# adjustable_biasing_pots.net
KiCad netlist of a schematic drawn in Altium Designer
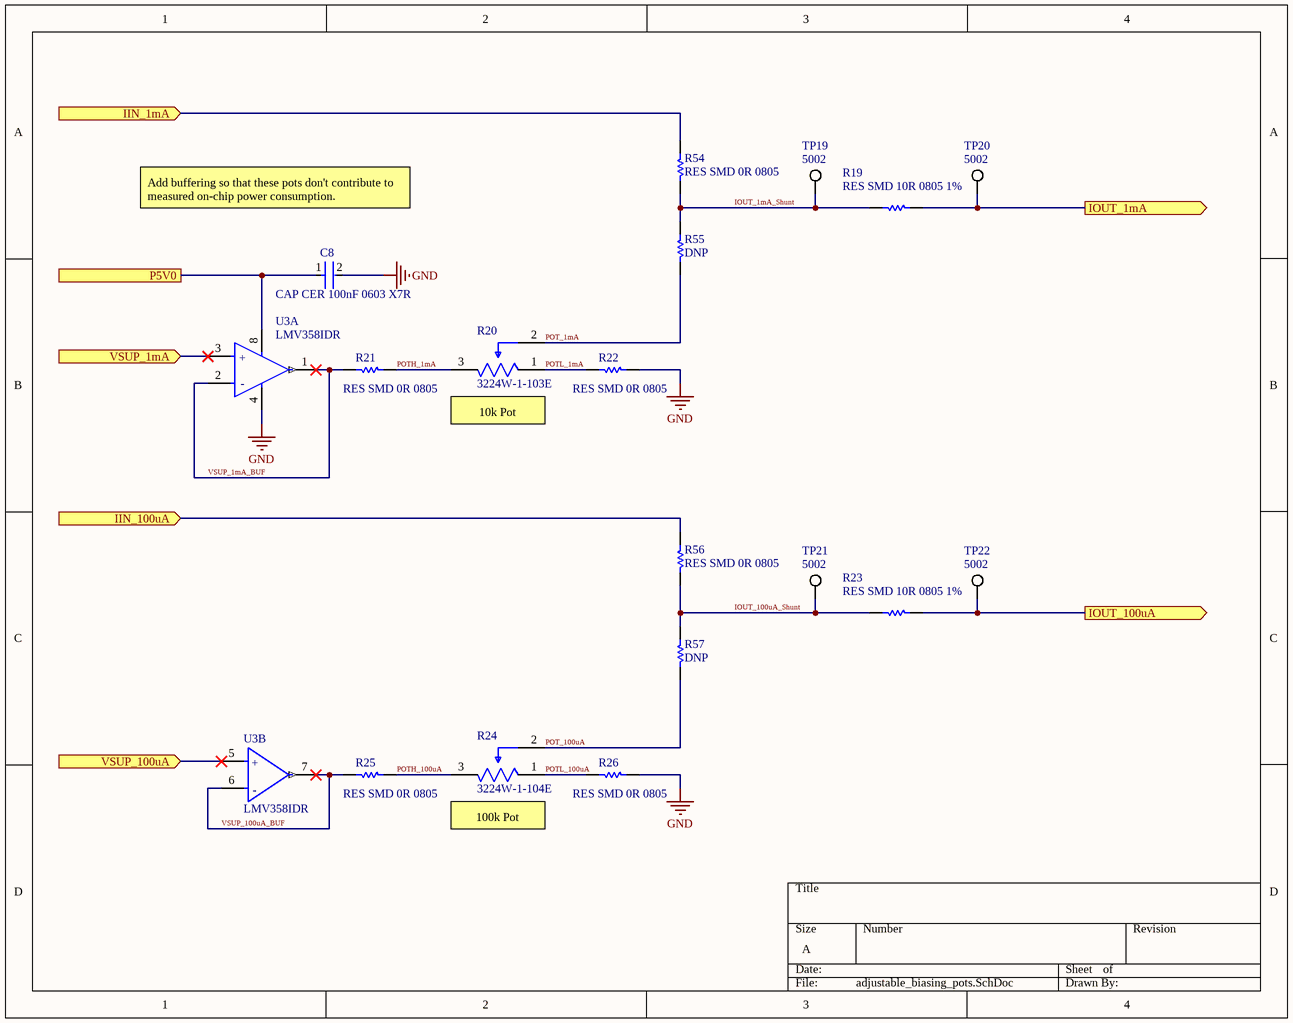
[diagram p0: adjustable_biasing_pots.SchDoc]

(export (version "E")
  (design (tool "Eeschema 10.0.6"))
  (components
    (comp (ref "C8")
      (value "CAP CER 100nF 0603 X7R")
      (footprint "FP-CC0603-DA-MFG")
      (description "CAP CER 0.1UF 16V X7R 0603")
      (fields
        (field (name "OCTOPART") "https://octopart.com/cc0603krx7r7bb104-yageo-192941")
        (field (name "TOLERANCE") "0.1")
      )
      (libsource (lib "Altium Content Vault") (part "11868f565c42a9108669ba33697ecf6"))
    )
    (comp (ref "R19")
      (value "RES SMD 10R 0805 1%")
      (footprint "RESC2013X55X40NL15T20")
      (fields (field (name "MANUFACTURER") "Vishay Dale") (field (name "PART NUMBER") "TNPW0805100RBEEA"))
      (libsource (lib "Altium Content Vault") (part "RES"))
    )
    (comp (ref "R20")
      (value "3224W-1-103E")
      (footprint "FP-3224W-MFG")
      (description "TRIMMER 10K OHM 0.25W J LEAD TOP")
      (fields (field (name "TOLERANCE") "10%") (field (name "MANUFACTURER") "Bourns"))
      (libsource (lib "Altium Content Vault") (part "83d3d349ed884d1db45cec512f27eb6"))
    )
    (comp (ref "R21")
      (value "RES SMD 0R 0805")
      (footprint "RESC2013X55X40NL15T20")
      (fields (field (name "MANUFACTURER") "Vishay Dale") (field (name "PART NUMBER") "TNPW0805100RBEEA"))
      (libsource (lib "Altium Content Vault") (part "RES"))
    )
    (comp (ref "R22")
      (value "RES SMD 0R 0805")
      (footprint "RESC2013X55X40NL15T20")
      (fields (field (name "MANUFACTURER") "Vishay Dale") (field (name "PART NUMBER") "TNPW0805100RBEEA"))
      (libsource (lib "Altium Content Vault") (part "RES"))
    )
    (comp (ref "R23")
      (value "RES SMD 10R 0805 1%")
      (footprint "RESC2013X55X40NL15T20")
      (fields (field (name "MANUFACTURER") "Vishay Dale") (field (name "PART NUMBER") "TNPW0805100RBEEA"))
      (libsource (lib "Altium Content Vault") (part "RES"))
    )
    (comp (ref "R24")
      (value "3224W-1-104E")
      (footprint "FP-3224W-MFG")
      (description "TRIMMER 10K OHM 0.25W J LEAD TOP")
      (fields (field (name "TOLERANCE") "10%") (field (name "MANUFACTURER") "Bourns"))
      (libsource (lib "Altium Content Vault") (part "83d3d349ed884d1db45cec512f27eb6"))
    )
    (comp (ref "R25")
      (value "RES SMD 0R 0805")
      (footprint "RESC2013X55X40NL15T20")
      (fields (field (name "MANUFACTURER") "Vishay Dale") (field (name "PART NUMBER") "TNPW0805100RBEEA"))
      (libsource (lib "Altium Content Vault") (part "RES"))
    )
    (comp (ref "R26")
      (value "RES SMD 0R 0805")
      (footprint "RESC2013X55X40NL15T20")
      (fields (field (name "MANUFACTURER") "Vishay Dale") (field (name "PART NUMBER") "TNPW0805100RBEEA"))
      (libsource (lib "Altium Content Vault") (part "RES"))
    )
    (comp (ref "R54")
      (value "RES SMD 0R 0805")
      (footprint "RESC2013X55X40NL15T20")
      (fields (field (name "MANUFACTURER") "Vishay Dale") (field (name "PART NUMBER") "TNPW0805100RBEEA"))
      (libsource (lib "Altium Content Vault") (part "RES"))
    )
    (comp (ref "R55")
      (value "DNP")
      (footprint "RESC2013X55X40NL15T20")
      (fields (field (name "MANUFACTURER") "Vishay Dale") (field (name "PART NUMBER") "TNPW0805100RBEEA"))
      (libsource (lib "Altium Content Vault") (part "RES"))
    )
    (comp (ref "R56")
      (value "RES SMD 0R 0805")
      (footprint "RESC2013X55X40NL15T20")
      (fields (field (name "MANUFACTURER") "Vishay Dale") (field (name "PART NUMBER") "TNPW0805100RBEEA"))
      (libsource (lib "Altium Content Vault") (part "RES"))
    )
    (comp (ref "R57")
      (value "DNP")
      (footprint "RESC2013X55X40NL15T20")
      (fields (field (name "MANUFACTURER") "Vishay Dale") (field (name "PART NUMBER") "TNPW0805100RBEEA"))
      (libsource (lib "Altium Content Vault") (part "RES"))
    )
    (comp (ref "TP19")
      (value "5002")
      (footprint "KSTN-5002")
      (description "Test Point, White, 1-Pin THD, RoHS, Bulk")
      (fields (field (name "MANUFACTURER") "KeystoneElectronics"))
      (libsource (lib "Altium Content Vault") (part "KSTN-TP-5002"))
    )
    (comp (ref "TP20")
      (value "5002")
      (footprint "KSTN-5002")
      (description "Test Point, White, 1-Pin THD, RoHS, Bulk")
      (fields (field (name "MANUFACTURER") "KeystoneElectronics"))
      (libsource (lib "Altium Content Vault") (part "KSTN-TP-5002"))
    )
    (comp (ref "TP21")
      (value "5002")
      (footprint "KSTN-5002")
      (description "Test Point, White, 1-Pin THD, RoHS, Bulk")
      (fields (field (name "MANUFACTURER") "KeystoneElectronics"))
      (libsource (lib "Altium Content Vault") (part "KSTN-TP-5002"))
    )
    (comp (ref "TP22")
      (value "5002")
      (footprint "KSTN-5002")
      (description "Test Point, White, 1-Pin THD, RoHS, Bulk")
      (fields (field (name "MANUFACTURER") "KeystoneElectronics"))
      (libsource (lib "Altium Content Vault") (part "KSTN-TP-5002"))
    )
    (comp (ref "U3")
      (value "LMV358IDR")
      (footprint "FP-D0008A-MFG")
      (description "IC OPAMP GP 2 CIRCUIT 8SOIC")
      (libsource (lib "Altium Content Vault") (part "1f85fec4e6914445158f776dbf16c1d"))
    )
  )
  (nets
    (net (code "1") (name "/IIN_1mA") (class "Default")
      (node (ref "R54") (pin "2") (pinfunction "2_2") (pintype "passive"))
    )
    (net (code "2") (name "/IIN_100uA") (class "Default")
      (node (ref "R56") (pin "2") (pinfunction "2_2") (pintype "passive"))
    )
    (net (code "3") (name "/IOUT_1mA") (class "Default")
      (node (ref "R19") (pin "2") (pinfunction "2_2") (pintype "passive"))
      (node (ref "TP20") (pin "1") (pintype "passive"))
    )
    (net (code "4") (name "/IOUT_1mA_Shunt") (class "Default")
      (node (ref "R19") (pin "1") (pinfunction "1_1") (pintype "passive"))
      (node (ref "R54") (pin "1") (pinfunction "1_1") (pintype "passive"))
      (node (ref "R55") (pin "2") (pinfunction "2_2") (pintype "passive"))
      (node (ref "TP19") (pin "1") (pintype "passive"))
    )
    (net (code "5") (name "/IOUT_100uA") (class "Default")
      (node (ref "R23") (pin "2") (pinfunction "2_2") (pintype "passive"))
      (node (ref "TP22") (pin "1") (pintype "passive"))
    )
    (net (code "6") (name "/IOUT_100uA_Shunt") (class "Default")
      (node (ref "R23") (pin "1") (pinfunction "1_1") (pintype "passive"))
      (node (ref "R56") (pin "1") (pinfunction "1_1") (pintype "passive"))
      (node (ref "R57") (pin "2") (pinfunction "2_2") (pintype "passive"))
      (node (ref "TP21") (pin "1") (pintype "passive"))
    )
    (net (code "7") (name "/P5V0") (class "Default")
      (node (ref "C8") (pin "1") (pinfunction "1_1") (pintype "passive"))
      (node (ref "U3") (pin "8") (pinfunction "VCC+_8") (pintype "power_in"))
    )
    (net (code "8") (name "/POTH_1mA") (class "Default")
      (node (ref "R20") (pin "3") (pinfunction "CW_3") (pintype "passive"))
      (node (ref "R21") (pin "2") (pinfunction "2_2") (pintype "passive"))
    )
    (net (code "9") (name "/POTH_100uA") (class "Default")
      (node (ref "R24") (pin "3") (pinfunction "CW_3") (pintype "passive"))
      (node (ref "R25") (pin "2") (pinfunction "2_2") (pintype "passive"))
    )
    (net (code "10") (name "/POTL_1mA") (class "Default")
      (node (ref "R20") (pin "1") (pinfunction "CCW_1") (pintype "passive"))
      (node (ref "R22") (pin "1") (pinfunction "1_1") (pintype "passive"))
    )
    (net (code "11") (name "/POTL_100uA") (class "Default")
      (node (ref "R24") (pin "1") (pinfunction "CCW_1") (pintype "passive"))
      (node (ref "R26") (pin "1") (pinfunction "1_1") (pintype "passive"))
    )
    (net (code "12") (name "/POT_1mA") (class "Default")
      (node (ref "R20") (pin "2") (pinfunction "WIPER_2") (pintype "passive"))
      (node (ref "R55") (pin "1") (pinfunction "1_1") (pintype "passive"))
    )
    (net (code "13") (name "/POT_100uA") (class "Default")
      (node (ref "R24") (pin "2") (pinfunction "WIPER_2") (pintype "passive"))
      (node (ref "R57") (pin "1") (pinfunction "1_1") (pintype "passive"))
    )
    (net (code "14") (name "/VSUP_1mA") (class "Default")
      (node (ref "U3") (pin "3") (pinfunction "1IN+_3") (pintype "tri_state+no_connect"))
    )
    (net (code "15") (name "/VSUP_1mA_BUF") (class "Default")
      (node (ref "R21") (pin "1") (pinfunction "1_1") (pintype "passive"))
      (node (ref "U3") (pin "1") (pinfunction "OUT_1") (pintype "output"))
      (node (ref "U3") (pin "2") (pinfunction "1IN-_2") (pintype "tri_state"))
    )
    (net (code "16") (name "/VSUP_100uA") (class "Default")
      (node (ref "U3") (pin "5") (pinfunction "2IN+_5") (pintype "tri_state+no_connect"))
    )
    (net (code "17") (name "/VSUP_100uA_BUF") (class "Default")
      (node (ref "R25") (pin "1") (pinfunction "1_1") (pintype "passive"))
      (node (ref "U3") (pin "6") (pinfunction "2IN-_6") (pintype "tri_state"))
      (node (ref "U3") (pin "7") (pinfunction "2OUT_7") (pintype "output"))
    )
    (net (code "18") (name "GND") (class "Default")
      (node (ref "C8") (pin "2") (pinfunction "2_2") (pintype "passive"))
      (node (ref "R22") (pin "2") (pinfunction "2_2") (pintype "passive"))
      (node (ref "R26") (pin "2") (pinfunction "2_2") (pintype "passive"))
      (node (ref "U3") (pin "4") (pinfunction "GND_4") (pintype "power_in"))
    )
  )
)
